# Gamer.net
KiCad netlist of a schematic drawn in EAGLE
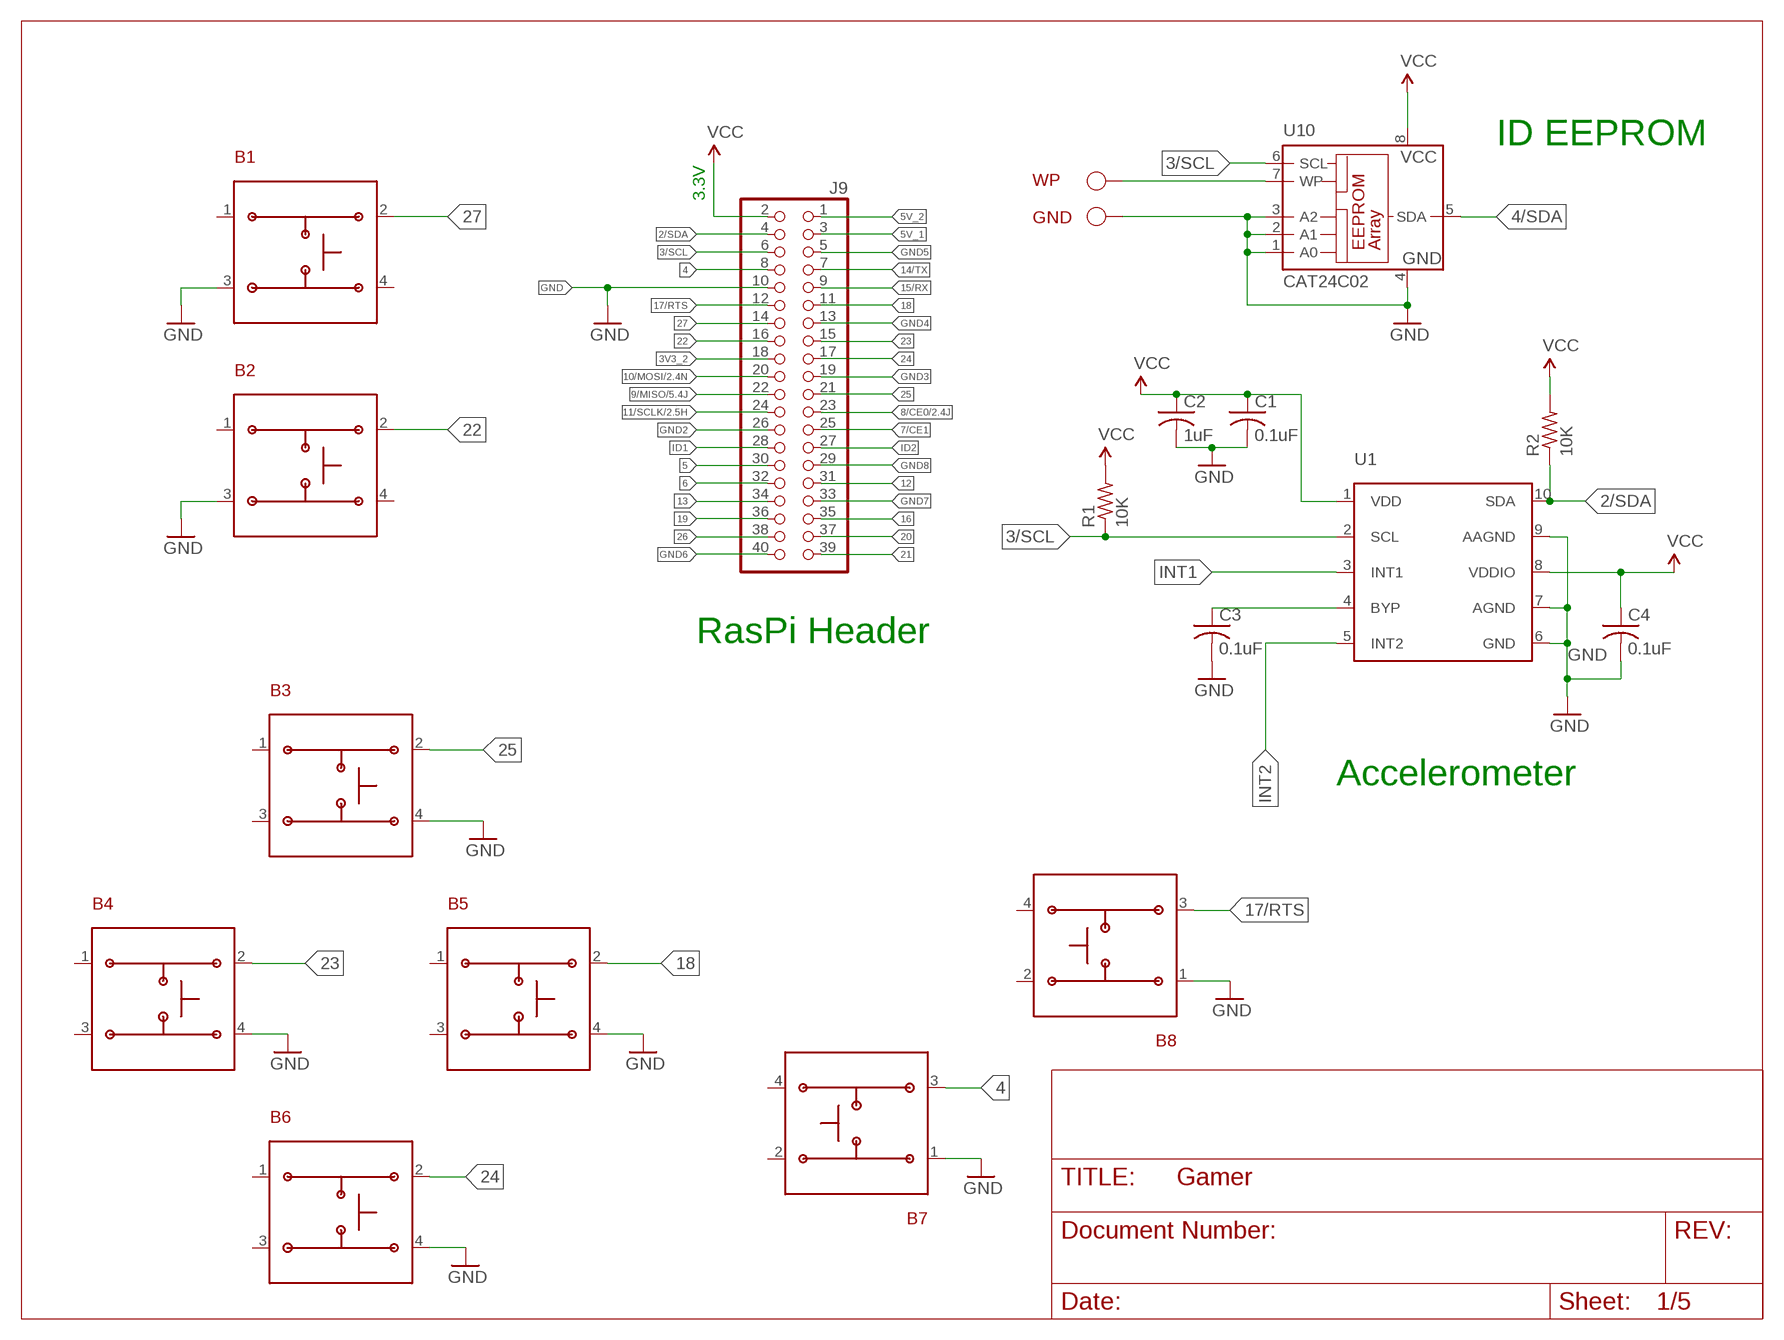
[diagram p0: schematic, sheet 1]
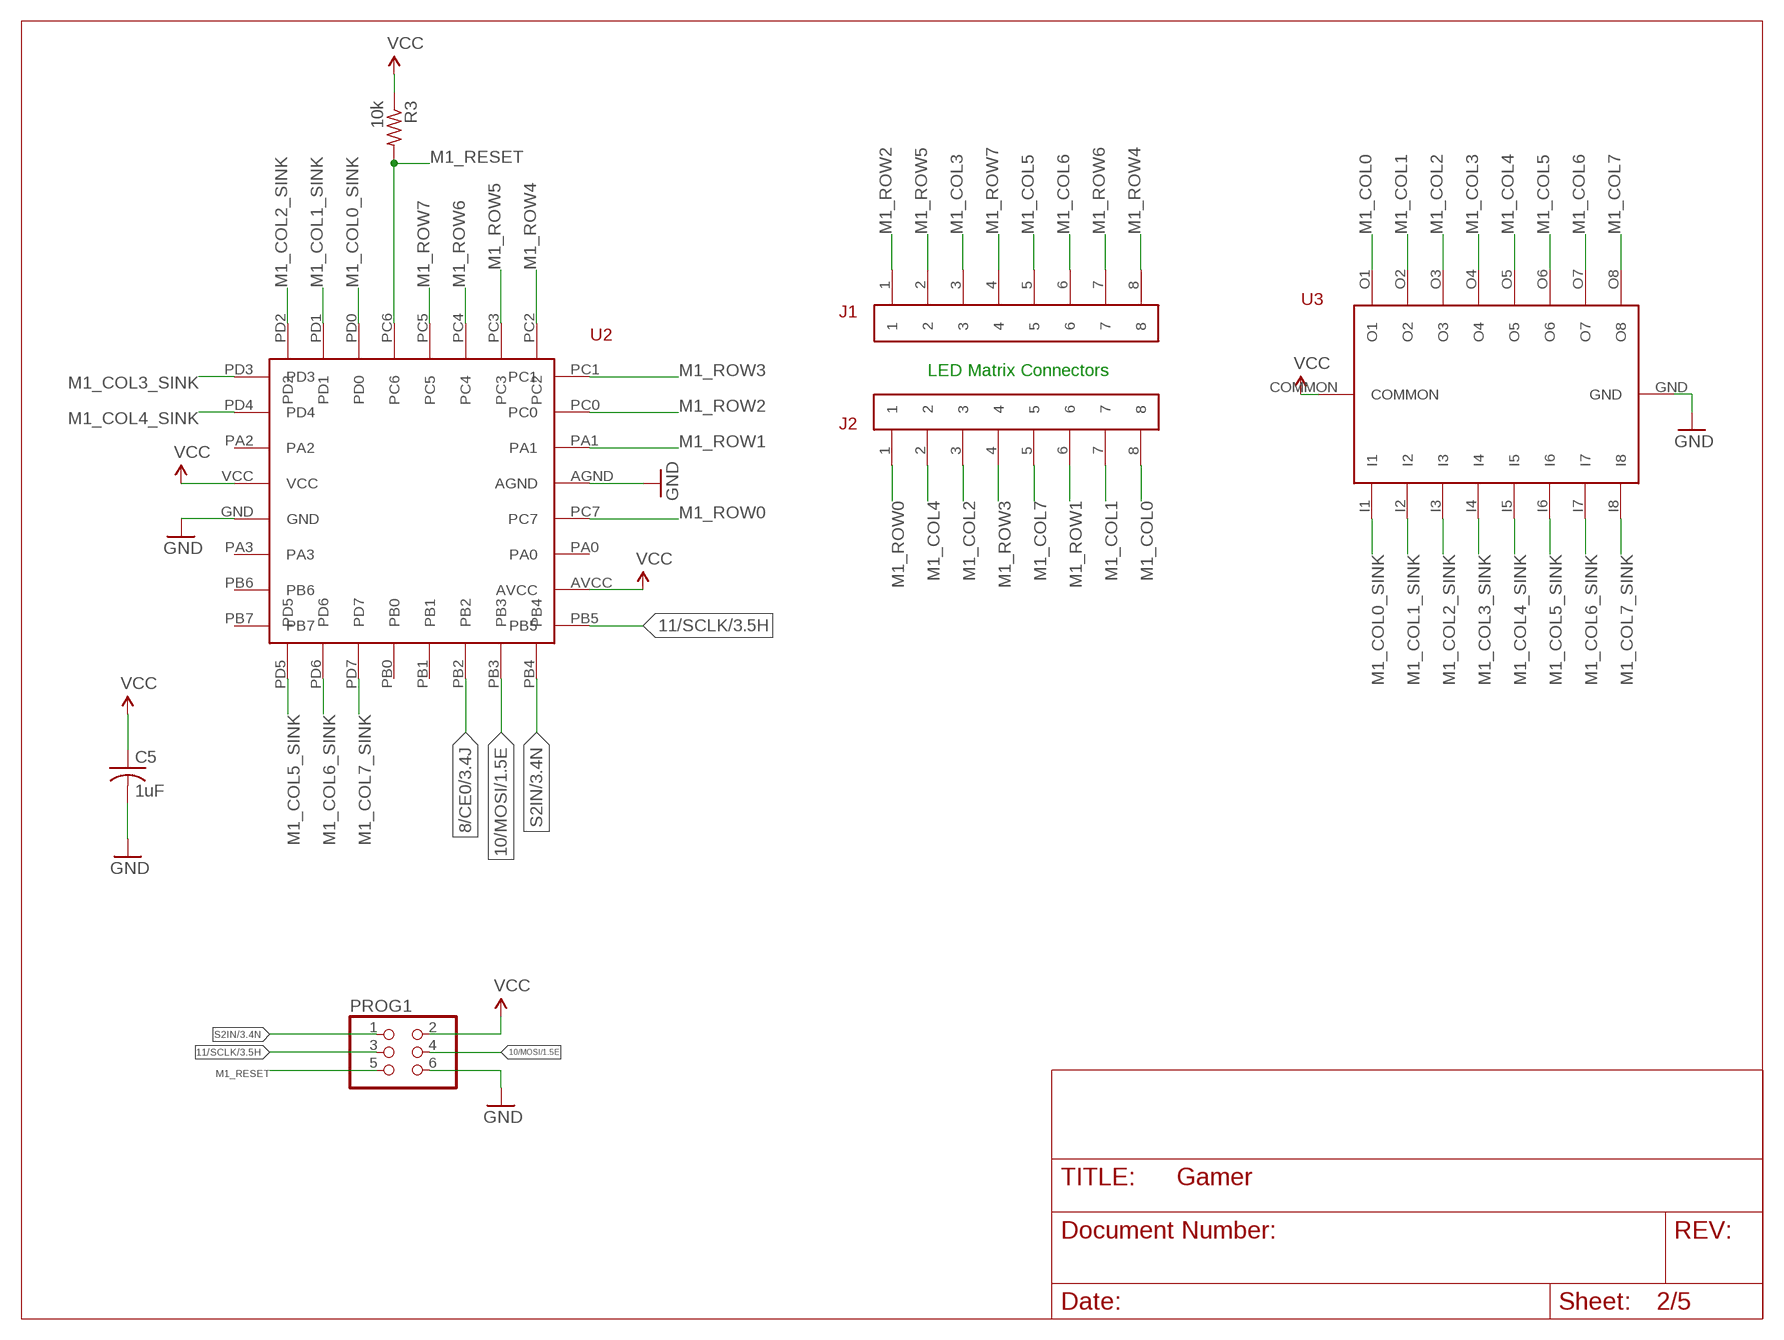
[diagram p1: schematic, sheet 2]
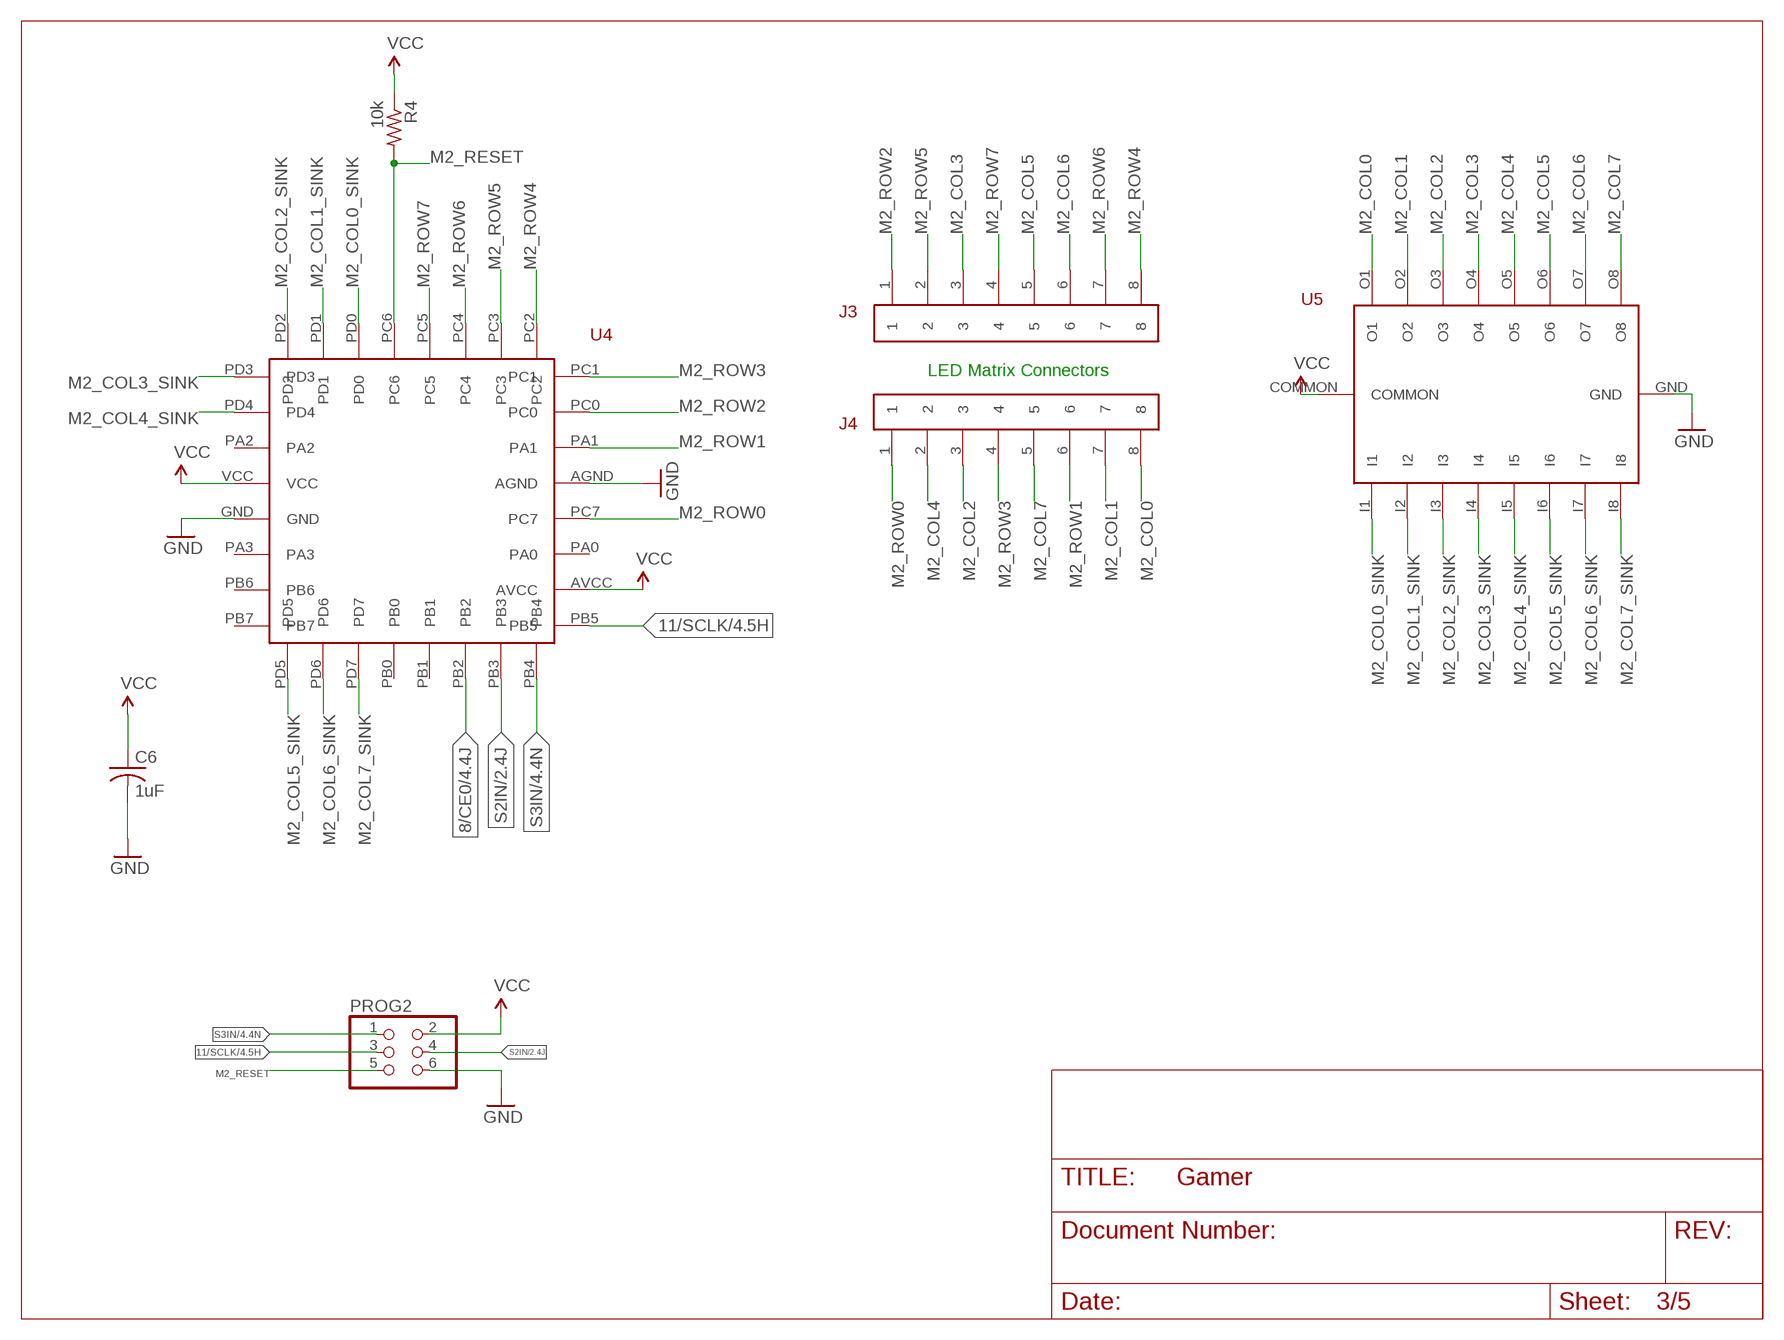
[diagram p2: schematic, sheet 3]
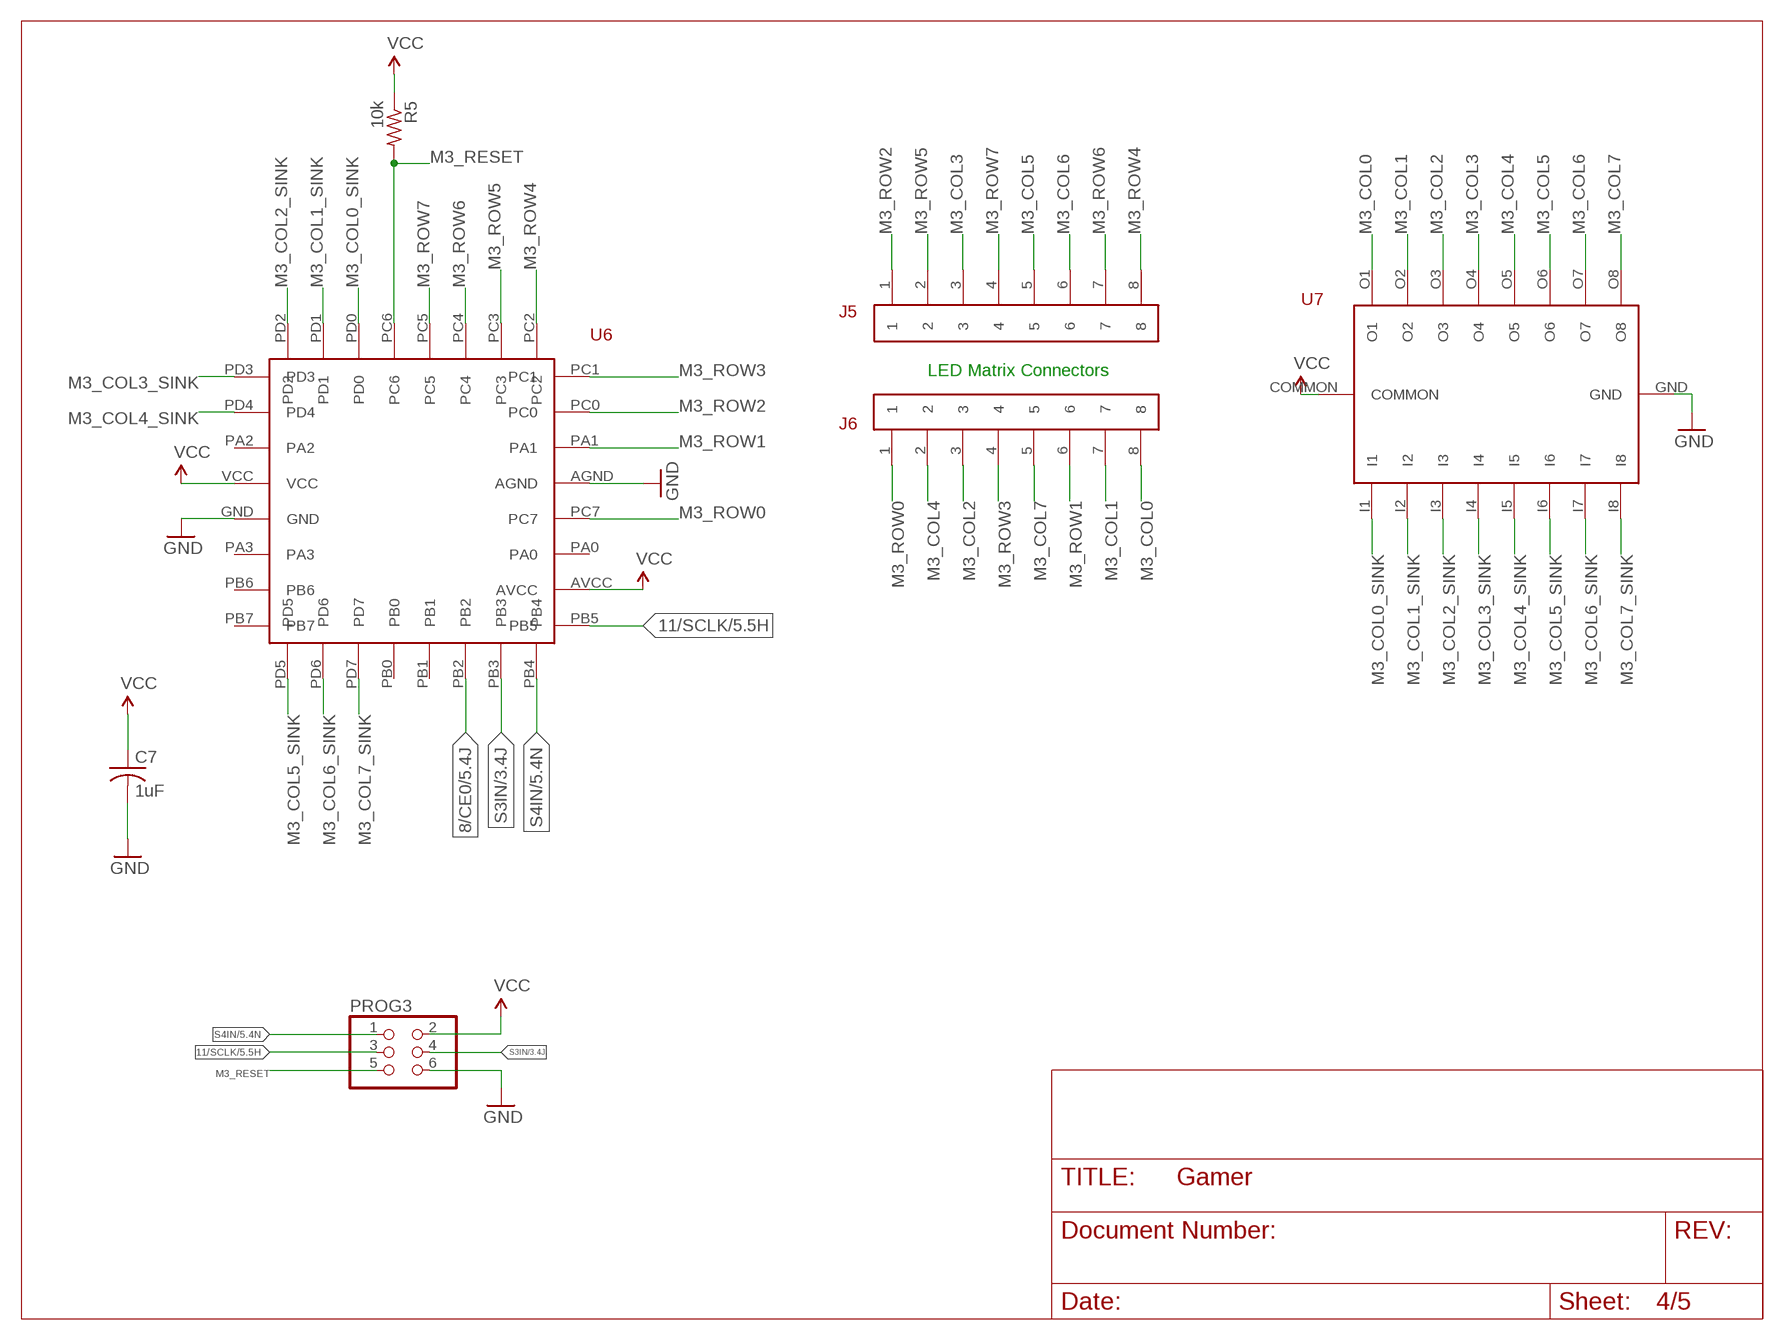
[diagram p3: schematic, sheet 4]
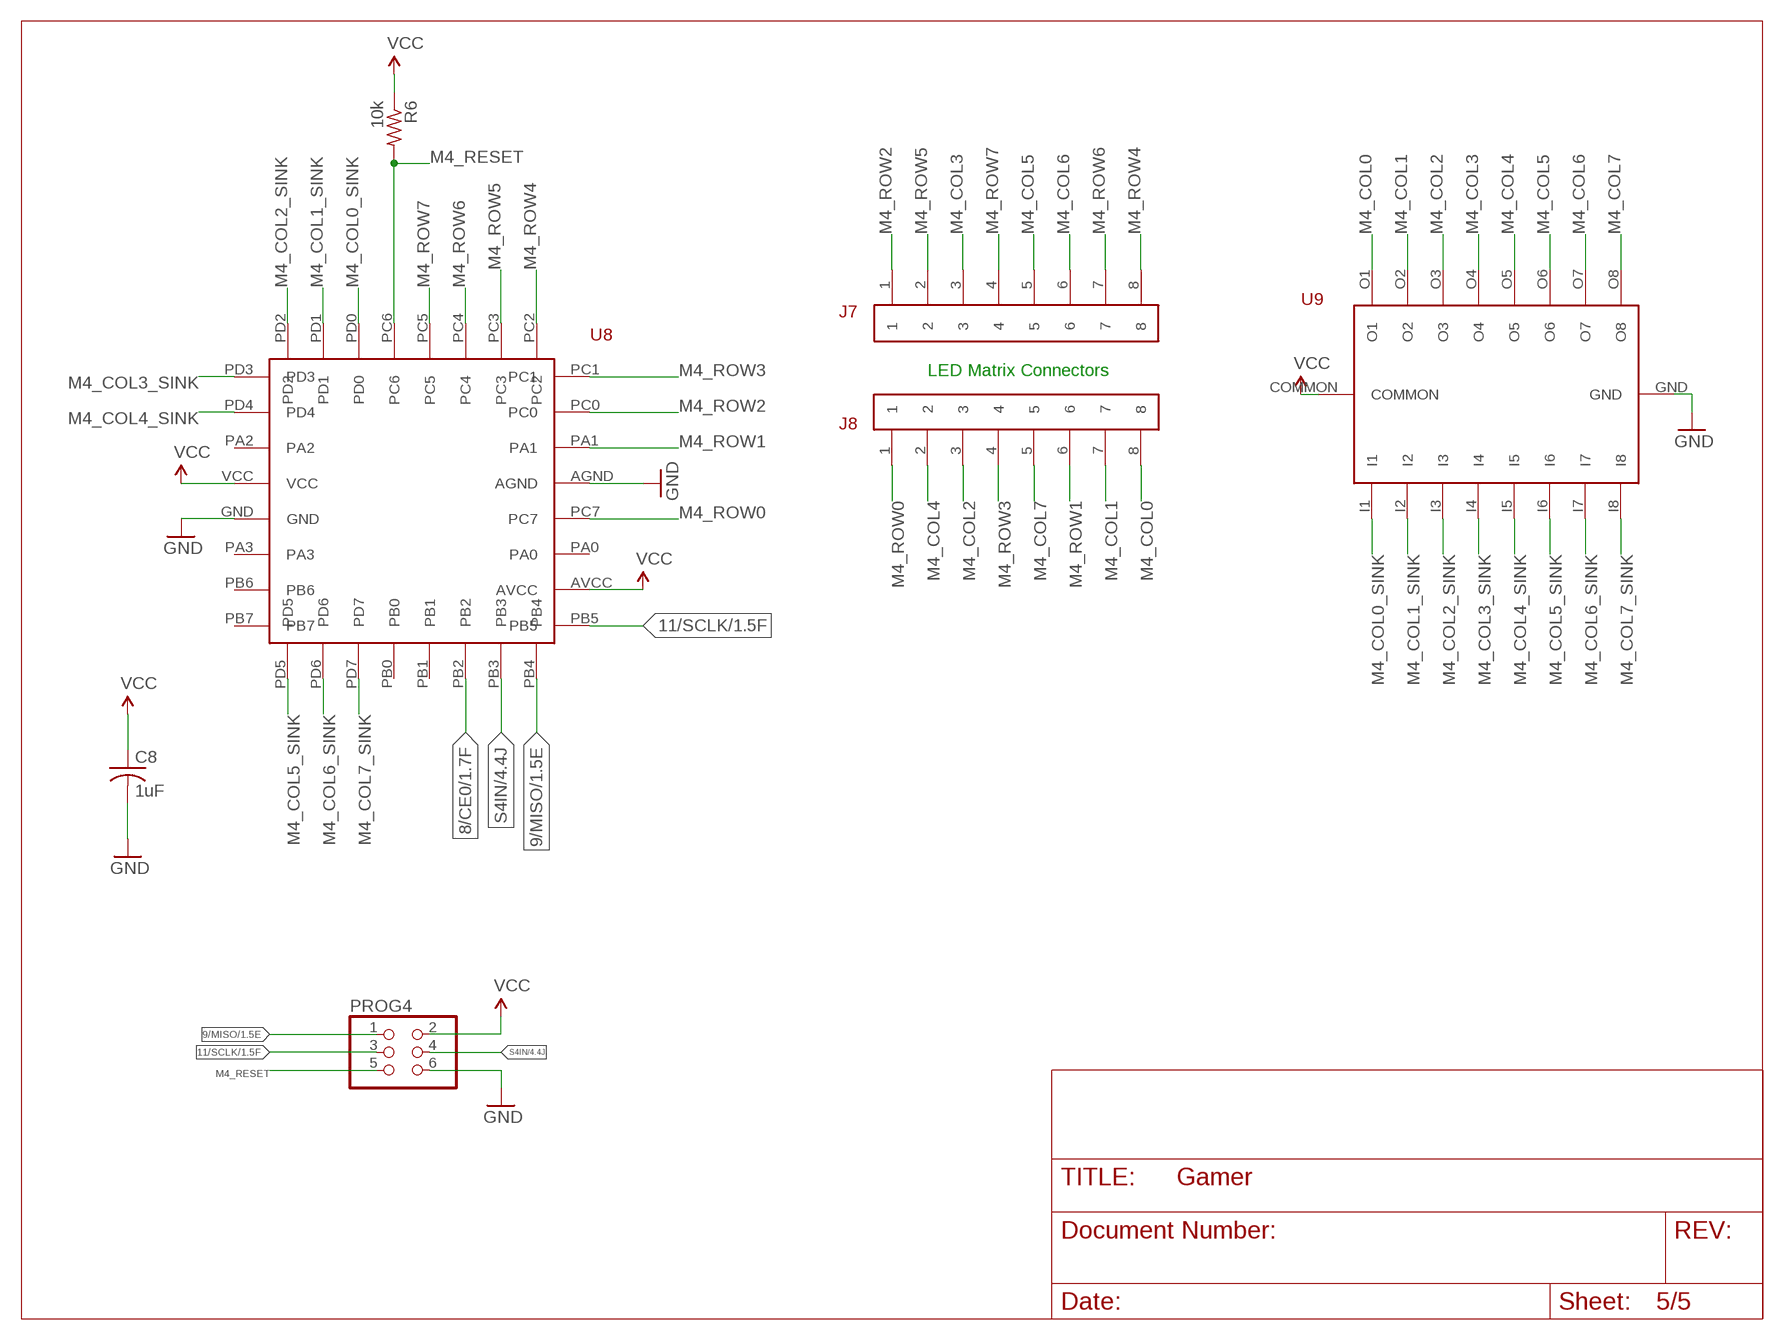
[diagram p4: schematic, sheet 5]

(export (version "E")
  (design (tool "Eeschema 10.0.6"))
  (components
    (comp (ref "C5")
      (value "1uF")
      (footprint "eagle-import:C0603")
      (libsource (lib "eagle-import") (part "resistor_C-USC0603"))
    )
    (comp (ref "J1")
      (value "HEADER-1X8")
      (footprint "eagle-import:HEADER-1X8")
      (libsource (lib "eagle-import") (part "HEADER-1X8"))
    )
    (comp (ref "J2")
      (value "HEADER-1X8")
      (footprint "eagle-import:HEADER-1X8")
      (libsource (lib "eagle-import") (part "HEADER-1X8"))
    )
    (comp (ref "PROG1")
      (value "NONE")
      (footprint "eagle-import:2X03")
      (libsource (lib "eagle-import") (part "PINHD-2X3"))
    )
    (comp (ref "R3")
      (value "10k")
      (footprint "eagle-import:R0603")
      (libsource (lib "eagle-import") (part "resistor_R-US_R0603"))
    )
    (comp (ref "U2")
      (value "ATTINY48")
      (footprint "eagle-import:ATTINY48")
      (libsource (lib "eagle-import") (part "ATTINY48"))
    )
    (comp (ref "U3")
      (value "ULN2803AFWG")
      (footprint "eagle-import:ULN2803AFWG")
      (libsource (lib "eagle-import") (part "ULN2803AFWG"))
    )
    (comp (ref "C6")
      (value "1uF")
      (footprint "eagle-import:C0603")
      (libsource (lib "eagle-import") (part "resistor_C-USC0603"))
    )
    (comp (ref "J3")
      (value "HEADER-1X8")
      (footprint "eagle-import:HEADER-1X8")
      (libsource (lib "eagle-import") (part "HEADER-1X8"))
    )
    (comp (ref "J4")
      (value "HEADER-1X8")
      (footprint "eagle-import:HEADER-1X8")
      (libsource (lib "eagle-import") (part "HEADER-1X8"))
    )
    (comp (ref "PROG2")
      (value "NONE")
      (footprint "eagle-import:2X03")
      (libsource (lib "eagle-import") (part "PINHD-2X3"))
    )
    (comp (ref "R4")
      (value "10k")
      (footprint "eagle-import:R0603")
      (libsource (lib "eagle-import") (part "resistor_R-US_R0603"))
    )
    (comp (ref "U4")
      (value "ATTINY48")
      (footprint "eagle-import:ATTINY48")
      (libsource (lib "eagle-import") (part "ATTINY48"))
    )
    (comp (ref "U5")
      (value "ULN2803AFWG")
      (footprint "eagle-import:ULN2803AFWG")
      (libsource (lib "eagle-import") (part "ULN2803AFWG"))
    )
    (comp (ref "B1")
      (value "6X6MM_BUTTON")
      (footprint "eagle-import:6X6MM_BUTTON")
      (libsource (lib "eagle-import") (part "6X6MM_BUTTON"))
    )
    (comp (ref "B2")
      (value "6X6MM_BUTTON")
      (footprint "eagle-import:6X6MM_BUTTON")
      (libsource (lib "eagle-import") (part "6X6MM_BUTTON"))
    )
    (comp (ref "B3")
      (value "12X12MM_BUTTON")
      (footprint "eagle-import:12X12MM_BUTTON")
      (libsource (lib "eagle-import") (part "12X12MM_BUTTON"))
    )
    (comp (ref "B4")
      (value "12X12MM_BUTTON")
      (footprint "eagle-import:12X12MM_BUTTON")
      (libsource (lib "eagle-import") (part "12X12MM_BUTTON"))
    )
    (comp (ref "B5")
      (value "12X12MM_BUTTON")
      (footprint "eagle-import:12X12MM_BUTTON")
      (libsource (lib "eagle-import") (part "12X12MM_BUTTON"))
    )
    (comp (ref "B6")
      (value "12X12MM_BUTTON")
      (footprint "eagle-import:12X12MM_BUTTON")
      (libsource (lib "eagle-import") (part "12X12MM_BUTTON"))
    )
    (comp (ref "B7")
      (value "12X12MM_BUTTON")
      (footprint "eagle-import:12X12MM_BUTTON")
      (libsource (lib "eagle-import") (part "12X12MM_BUTTON"))
    )
    (comp (ref "B8")
      (value "12X12MM_BUTTON")
      (footprint "eagle-import:12X12MM_BUTTON")
      (libsource (lib "eagle-import") (part "12X12MM_BUTTON"))
    )
    (comp (ref "C1")
      (value "0.1uF")
      (footprint "eagle-import:C0603")
      (libsource (lib "eagle-import") (part "C-USC0603"))
    )
    (comp (ref "C2")
      (value "1uF")
      (footprint "eagle-import:C0603")
      (libsource (lib "eagle-import") (part "C-USC0603"))
    )
    (comp (ref "C3")
      (value "0.1uF")
      (footprint "eagle-import:C0603")
      (libsource (lib "eagle-import") (part "C-USC0603"))
    )
    (comp (ref "C4")
      (value "0.1uF")
      (footprint "eagle-import:C0603")
      (libsource (lib "eagle-import") (part "C-USC0603"))
    )
    (comp (ref "GND")
      (value "TESTPAD")
      (footprint "eagle-import:TESTPAD")
      (libsource (lib "eagle-import") (part "TESTPAD"))
    )
    (comp (ref "J9")
      (value "PINHD-2X20")
      (footprint "eagle-import:2X20")
      (libsource (lib "eagle-import") (part "PINHD-2X20"))
    )
    (comp (ref "R1")
      (value "10K")
      (footprint "eagle-import:R0603")
      (libsource (lib "eagle-import") (part "R-US_R0603"))
    )
    (comp (ref "R2")
      (value "10K")
      (footprint "eagle-import:R0603")
      (libsource (lib "eagle-import") (part "R-US_R0603"))
    )
    (comp (ref "U1")
      (value "MMA8653FCR1")
      (footprint "eagle-import:MMA8653FCR1")
      (libsource (lib "eagle-import") (part "MMA8653FCR1"))
    )
    (comp (ref "U10")
      (value "CAT24C02")
      (footprint "eagle-import:TSSOP8")
      (fields (field (name "MF") "MICROCHIP") (field (name "MPN") "24LC64X-I/ST"))
      (libsource (lib "eagle-import") (part "24STLC64"))
    )
    (comp (ref "WP")
      (value "TESTPAD")
      (footprint "eagle-import:TESTPAD")
      (libsource (lib "eagle-import") (part "TESTPAD"))
    )
    (comp (ref "C7")
      (value "1uF")
      (footprint "eagle-import:C0603")
      (libsource (lib "eagle-import") (part "resistor_C-USC0603"))
    )
    (comp (ref "J5")
      (value "HEADER-1X8")
      (footprint "eagle-import:HEADER-1X8")
      (libsource (lib "eagle-import") (part "HEADER-1X8"))
    )
    (comp (ref "J6")
      (value "HEADER-1X8")
      (footprint "eagle-import:HEADER-1X8")
      (libsource (lib "eagle-import") (part "HEADER-1X8"))
    )
    (comp (ref "PROG3")
      (value "NONE")
      (footprint "eagle-import:2X03")
      (libsource (lib "eagle-import") (part "PINHD-2X3"))
    )
    (comp (ref "R5")
      (value "10k")
      (footprint "eagle-import:R0603")
      (libsource (lib "eagle-import") (part "resistor_R-US_R0603"))
    )
    (comp (ref "U6")
      (value "ATTINY48")
      (footprint "eagle-import:ATTINY48")
      (libsource (lib "eagle-import") (part "ATTINY48"))
    )
    (comp (ref "U7")
      (value "ULN2803AFWG")
      (footprint "eagle-import:ULN2803AFWG")
      (libsource (lib "eagle-import") (part "ULN2803AFWG"))
    )
    (comp (ref "C8")
      (value "1uF")
      (footprint "eagle-import:C0603")
      (libsource (lib "eagle-import") (part "resistor_C-USC0603"))
    )
    (comp (ref "J7")
      (value "HEADER-1X8")
      (footprint "eagle-import:HEADER-1X8")
      (libsource (lib "eagle-import") (part "HEADER-1X8"))
    )
    (comp (ref "J8")
      (value "HEADER-1X8")
      (footprint "eagle-import:HEADER-1X8")
      (libsource (lib "eagle-import") (part "HEADER-1X8"))
    )
    (comp (ref "PROG4")
      (value "NONE")
      (footprint "eagle-import:2X03")
      (libsource (lib "eagle-import") (part "PINHD-2X3"))
    )
    (comp (ref "R6")
      (value "10k")
      (footprint "eagle-import:R0603")
      (libsource (lib "eagle-import") (part "resistor_R-US_R0603"))
    )
    (comp (ref "U8")
      (value "ATTINY48")
      (footprint "eagle-import:ATTINY48")
      (libsource (lib "eagle-import") (part "ATTINY48"))
    )
    (comp (ref "U9")
      (value "ULN2803AFWG")
      (footprint "eagle-import:ULN2803AFWG")
      (libsource (lib "eagle-import") (part "ULN2803AFWG"))
    )
  )
  (nets
    (net (code "1") (name "2{slash}SDA") (class "Default")
      (node (ref "J9") (pin "4") (pinfunction "4_4") (pintype "passive"))
      (node (ref "R2") (pin "1") (pinfunction "1_1") (pintype "passive"))
      (node (ref "U1") (pin "10") (pinfunction "SDA_10") (pintype "bidirectional"))
    )
    (net (code "2") (name "3V3_2") (class "Default")
      (node (ref "J9") (pin "18") (pinfunction "18_18") (pintype "passive"))
    )
    (net (code "3") (name "3{slash}SCL") (class "Default")
      (node (ref "J9") (pin "6") (pinfunction "6_6") (pintype "passive"))
      (node (ref "R1") (pin "1") (pinfunction "1_1") (pintype "passive"))
      (node (ref "U1") (pin "2") (pinfunction "SCL_2") (pintype "bidirectional"))
      (node (ref "U10") (pin "6") (pinfunction "SCL_6") (pintype "input"))
    )
    (net (code "4") (name "4") (class "Default")
      (node (ref "B7") (pin "3") (pinfunction "3_3") (pintype "bidirectional"))
      (node (ref "J9") (pin "8") (pinfunction "8_8") (pintype "passive"))
    )
    (net (code "5") (name "4{slash}SDA") (class "Default")
      (node (ref "U10") (pin "5") (pinfunction "SDA_5") (pintype "bidirectional"))
    )
    (net (code "6") (name "5") (class "Default")
      (node (ref "J9") (pin "30") (pinfunction "30_30") (pintype "passive"))
    )
    (net (code "7") (name "5V_1") (class "Default")
      (node (ref "J9") (pin "3") (pinfunction "3_3") (pintype "passive"))
    )
    (net (code "8") (name "5V_2") (class "Default")
      (node (ref "J9") (pin "1") (pinfunction "1_1") (pintype "passive"))
    )
    (net (code "9") (name "6") (class "Default")
      (node (ref "J9") (pin "32") (pinfunction "32_32") (pintype "passive"))
    )
    (net (code "10") (name "7{slash}CE1") (class "Default")
      (node (ref "J9") (pin "25") (pinfunction "25_25") (pintype "passive"))
    )
    (net (code "11") (name "8{slash}CE0") (class "Default")
      (node (ref "J9") (pin "23") (pinfunction "23_23") (pintype "passive"))
      (node (ref "U2") (pin "PB2") (pinfunction "PB2_PB2") (pintype "bidirectional"))
      (node (ref "U4") (pin "PB2") (pinfunction "PB2_PB2") (pintype "bidirectional"))
      (node (ref "U6") (pin "PB2") (pinfunction "PB2_PB2") (pintype "bidirectional"))
      (node (ref "U8") (pin "PB2") (pinfunction "PB2_PB2") (pintype "bidirectional"))
    )
    (net (code "12") (name "9{slash}MISO") (class "Default")
      (node (ref "J9") (pin "22") (pinfunction "22_22") (pintype "passive"))
      (node (ref "PROG4") (pin "1") (pinfunction "1_1") (pintype "passive"))
      (node (ref "U8") (pin "PB4") (pinfunction "PB4_PB4") (pintype "bidirectional"))
    )
    (net (code "13") (name "10{slash}MOSI") (class "Default")
      (node (ref "J9") (pin "20") (pinfunction "20_20") (pintype "passive"))
      (node (ref "PROG1") (pin "4") (pinfunction "4_4") (pintype "passive"))
      (node (ref "U2") (pin "PB3") (pinfunction "PB3_PB3") (pintype "bidirectional"))
    )
    (net (code "14") (name "11{slash}SCLK") (class "Default")
      (node (ref "J9") (pin "24") (pinfunction "24_24") (pintype "passive"))
      (node (ref "PROG1") (pin "3") (pinfunction "3_3") (pintype "passive"))
      (node (ref "PROG2") (pin "3") (pinfunction "3_3") (pintype "passive"))
      (node (ref "PROG3") (pin "3") (pinfunction "3_3") (pintype "passive"))
      (node (ref "PROG4") (pin "3") (pinfunction "3_3") (pintype "passive"))
      (node (ref "U2") (pin "PB5") (pinfunction "PB5_PB5") (pintype "bidirectional"))
      (node (ref "U4") (pin "PB5") (pinfunction "PB5_PB5") (pintype "bidirectional"))
      (node (ref "U6") (pin "PB5") (pinfunction "PB5_PB5") (pintype "bidirectional"))
      (node (ref "U8") (pin "PB5") (pinfunction "PB5_PB5") (pintype "bidirectional"))
    )
    (net (code "15") (name "12") (class "Default")
      (node (ref "J9") (pin "31") (pinfunction "31_31") (pintype "passive"))
    )
    (net (code "16") (name "13") (class "Default")
      (node (ref "J9") (pin "34") (pinfunction "34_34") (pintype "passive"))
    )
    (net (code "17") (name "14{slash}TX") (class "Default")
      (node (ref "J9") (pin "7") (pinfunction "7_7") (pintype "passive"))
    )
    (net (code "18") (name "15{slash}RX") (class "Default")
      (node (ref "J9") (pin "9") (pinfunction "9_9") (pintype "passive"))
    )
    (net (code "19") (name "16") (class "Default")
      (node (ref "J9") (pin "35") (pinfunction "35_35") (pintype "passive"))
    )
    (net (code "20") (name "17{slash}RTS") (class "Default")
      (node (ref "B8") (pin "3") (pinfunction "3_3") (pintype "bidirectional"))
      (node (ref "J9") (pin "12") (pinfunction "12_12") (pintype "passive"))
    )
    (net (code "21") (name "18") (class "Default")
      (node (ref "B5") (pin "2") (pinfunction "2_2") (pintype "bidirectional"))
      (node (ref "J9") (pin "11") (pinfunction "11_11") (pintype "passive"))
    )
    (net (code "22") (name "19") (class "Default")
      (node (ref "J9") (pin "36") (pinfunction "36_36") (pintype "passive"))
    )
    (net (code "23") (name "20") (class "Default")
      (node (ref "J9") (pin "37") (pinfunction "37_37") (pintype "passive"))
    )
    (net (code "24") (name "21") (class "Default")
      (node (ref "J9") (pin "39") (pinfunction "39_39") (pintype "passive"))
    )
    (net (code "25") (name "22") (class "Default")
      (node (ref "B2") (pin "2") (pinfunction "2_2") (pintype "bidirectional"))
      (node (ref "J9") (pin "16") (pinfunction "16_16") (pintype "passive"))
    )
    (net (code "26") (name "23") (class "Default")
      (node (ref "B4") (pin "2") (pinfunction "2_2") (pintype "bidirectional"))
      (node (ref "J9") (pin "15") (pinfunction "15_15") (pintype "passive"))
    )
    (net (code "27") (name "24") (class "Default")
      (node (ref "B6") (pin "2") (pinfunction "2_2") (pintype "bidirectional"))
      (node (ref "J9") (pin "17") (pinfunction "17_17") (pintype "passive"))
    )
    (net (code "28") (name "25") (class "Default")
      (node (ref "B3") (pin "2") (pinfunction "2_2") (pintype "bidirectional"))
      (node (ref "J9") (pin "21") (pinfunction "21_21") (pintype "passive"))
    )
    (net (code "29") (name "26") (class "Default")
      (node (ref "J9") (pin "38") (pinfunction "38_38") (pintype "passive"))
    )
    (net (code "30") (name "27") (class "Default")
      (node (ref "B1") (pin "2") (pinfunction "2_2") (pintype "bidirectional"))
      (node (ref "J9") (pin "14") (pinfunction "14_14") (pintype "passive"))
    )
    (net (code "31") (name "GND") (class "Default")
      (node (ref "B1") (pin "3") (pinfunction "3_3") (pintype "bidirectional"))
      (node (ref "B2") (pin "3") (pinfunction "3_3") (pintype "bidirectional"))
      (node (ref "B3") (pin "4") (pinfunction "4_4") (pintype "bidirectional"))
      (node (ref "B4") (pin "4") (pinfunction "4_4") (pintype "bidirectional"))
      (node (ref "B5") (pin "4") (pinfunction "4_4") (pintype "bidirectional"))
      (node (ref "B6") (pin "4") (pinfunction "4_4") (pintype "bidirectional"))
      (node (ref "B7") (pin "1") (pinfunction "1_1") (pintype "bidirectional"))
      (node (ref "B8") (pin "1") (pinfunction "1_1") (pintype "bidirectional"))
      (node (ref "C1") (pin "2") (pinfunction "2_2") (pintype "passive"))
      (node (ref "C2") (pin "2") (pinfunction "2_2") (pintype "passive"))
      (node (ref "C3") (pin "2") (pinfunction "2_2") (pintype "passive"))
      (node (ref "C4") (pin "2") (pinfunction "2_2") (pintype "passive"))
      (node (ref "C5") (pin "2") (pinfunction "2_2") (pintype "passive"))
      (node (ref "C6") (pin "2") (pinfunction "2_2") (pintype "passive"))
      (node (ref "C7") (pin "2") (pinfunction "2_2") (pintype "passive"))
      (node (ref "C8") (pin "2") (pinfunction "2_2") (pintype "passive"))
      (node (ref "GND") (pin "1") (pinfunction "P$1_1") (pintype "bidirectional"))
      (node (ref "J9") (pin "10") (pinfunction "10_10") (pintype "passive"))
      (node (ref "PROG1") (pin "6") (pinfunction "6_6") (pintype "passive"))
      (node (ref "PROG2") (pin "6") (pinfunction "6_6") (pintype "passive"))
      (node (ref "PROG3") (pin "6") (pinfunction "6_6") (pintype "passive"))
      (node (ref "PROG4") (pin "6") (pinfunction "6_6") (pintype "passive"))
      (node (ref "U1") (pin "6") (pinfunction "GND_6") (pintype "bidirectional"))
      (node (ref "U1") (pin "7") (pinfunction "AGND_7") (pintype "bidirectional"))
      (node (ref "U1") (pin "9") (pinfunction "AAGND_9") (pintype "bidirectional"))
      (node (ref "U10") (pin "1") (pinfunction "A0_1") (pintype "input"))
      (node (ref "U10") (pin "2") (pinfunction "A1_2") (pintype "input"))
      (node (ref "U10") (pin "3") (pinfunction "A2_3") (pintype "input"))
      (node (ref "U10") (pin "4") (pinfunction "GND_4") (pintype "power_in"))
      (node (ref "U2") (pin "AGND") (pinfunction "AGND_AGND") (pintype "bidirectional"))
      (node (ref "U2") (pin "GND") (pinfunction "GND_GND") (pintype "bidirectional"))
      (node (ref "U3") (pin "GND") (pinfunction "GND_GND") (pintype "bidirectional"))
      (node (ref "U4") (pin "AGND") (pinfunction "AGND_AGND") (pintype "bidirectional"))
      (node (ref "U4") (pin "GND") (pinfunction "GND_GND") (pintype "bidirectional"))
      (node (ref "U5") (pin "GND") (pinfunction "GND_GND") (pintype "bidirectional"))
      (node (ref "U6") (pin "AGND") (pinfunction "AGND_AGND") (pintype "bidirectional"))
      (node (ref "U6") (pin "GND") (pinfunction "GND_GND") (pintype "bidirectional"))
      (node (ref "U7") (pin "GND") (pinfunction "GND_GND") (pintype "bidirectional"))
      (node (ref "U8") (pin "AGND") (pinfunction "AGND_AGND") (pintype "bidirectional"))
      (node (ref "U8") (pin "GND") (pinfunction "GND_GND") (pintype "bidirectional"))
      (node (ref "U9") (pin "GND") (pinfunction "GND_GND") (pintype "bidirectional"))
    )
    (net (code "32") (name "GND2") (class "Default")
      (node (ref "J9") (pin "26") (pinfunction "26_26") (pintype "passive"))
    )
    (net (code "33") (name "GND3") (class "Default")
      (node (ref "J9") (pin "19") (pinfunction "19_19") (pintype "passive"))
    )
    (net (code "34") (name "GND4") (class "Default")
      (node (ref "J9") (pin "13") (pinfunction "13_13") (pintype "passive"))
    )
    (net (code "35") (name "GND5") (class "Default")
      (node (ref "J9") (pin "5") (pinfunction "5_5") (pintype "passive"))
    )
    (net (code "36") (name "GND6") (class "Default")
      (node (ref "J9") (pin "40") (pinfunction "40_40") (pintype "passive"))
    )
    (net (code "37") (name "GND7") (class "Default")
      (node (ref "J9") (pin "33") (pinfunction "33_33") (pintype "passive"))
    )
    (net (code "38") (name "GND8") (class "Default")
      (node (ref "J9") (pin "29") (pinfunction "29_29") (pintype "passive"))
    )
    (net (code "39") (name "ID1") (class "Default")
      (node (ref "J9") (pin "28") (pinfunction "28_28") (pintype "passive"))
    )
    (net (code "40") (name "ID2") (class "Default")
      (node (ref "J9") (pin "27") (pinfunction "27_27") (pintype "passive"))
    )
    (net (code "41") (name "INT1") (class "Default")
      (node (ref "U1") (pin "3") (pinfunction "INT1_3") (pintype "bidirectional"))
    )
    (net (code "42") (name "INT2") (class "Default")
      (node (ref "U1") (pin "5") (pinfunction "INT2_5") (pintype "bidirectional"))
    )
    (net (code "43") (name "M1_COL0") (class "Default")
      (node (ref "J2") (pin "8") (pinfunction "8_8") (pintype "bidirectional"))
      (node (ref "U3") (pin "O1") (pinfunction "O1_O1") (pintype "bidirectional"))
    )
    (net (code "44") (name "M1_COL0_SINK") (class "Default")
      (node (ref "U2") (pin "PD0") (pinfunction "PD0_PD0") (pintype "bidirectional"))
      (node (ref "U3") (pin "I1") (pinfunction "I1_I1") (pintype "bidirectional"))
    )
    (net (code "45") (name "M1_COL1") (class "Default")
      (node (ref "J2") (pin "7") (pinfunction "7_7") (pintype "bidirectional"))
      (node (ref "U3") (pin "O2") (pinfunction "O2_O2") (pintype "bidirectional"))
    )
    (net (code "46") (name "M1_COL1_SINK") (class "Default")
      (node (ref "U2") (pin "PD1") (pinfunction "PD1_PD1") (pintype "bidirectional"))
      (node (ref "U3") (pin "I2") (pinfunction "I2_I2") (pintype "bidirectional"))
    )
    (net (code "47") (name "M1_COL2") (class "Default")
      (node (ref "J2") (pin "3") (pinfunction "3_3") (pintype "bidirectional"))
      (node (ref "U3") (pin "O3") (pinfunction "O3_O3") (pintype "bidirectional"))
    )
    (net (code "48") (name "M1_COL2_SINK") (class "Default")
      (node (ref "U2") (pin "PD2") (pinfunction "PD2_PD2") (pintype "bidirectional"))
      (node (ref "U3") (pin "I3") (pinfunction "I3_I3") (pintype "bidirectional"))
    )
    (net (code "49") (name "M1_COL3") (class "Default")
      (node (ref "J1") (pin "3") (pinfunction "3_3") (pintype "bidirectional"))
      (node (ref "U3") (pin "O4") (pinfunction "O4_O4") (pintype "bidirectional"))
    )
    (net (code "50") (name "M1_COL3_SINK") (class "Default")
      (node (ref "U2") (pin "PD3") (pinfunction "PD3_PD3") (pintype "bidirectional"))
      (node (ref "U3") (pin "I4") (pinfunction "I4_I4") (pintype "bidirectional"))
    )
    (net (code "51") (name "M1_COL4") (class "Default")
      (node (ref "J2") (pin "2") (pinfunction "2_2") (pintype "bidirectional"))
      (node (ref "U3") (pin "O5") (pinfunction "O5_O5") (pintype "bidirectional"))
    )
    (net (code "52") (name "M1_COL4_SINK") (class "Default")
      (node (ref "U2") (pin "PD4") (pinfunction "PD4_PD4") (pintype "bidirectional"))
      (node (ref "U3") (pin "I5") (pinfunction "I5_I5") (pintype "bidirectional"))
    )
    (net (code "53") (name "M1_COL5") (class "Default")
      (node (ref "J1") (pin "5") (pinfunction "5_5") (pintype "bidirectional"))
      (node (ref "U3") (pin "O6") (pinfunction "O6_O6") (pintype "bidirectional"))
    )
    (net (code "54") (name "M1_COL5_SINK") (class "Default")
      (node (ref "U2") (pin "PD5") (pinfunction "PD5_PD5") (pintype "bidirectional"))
      (node (ref "U3") (pin "I6") (pinfunction "I6_I6") (pintype "bidirectional"))
    )
    (net (code "55") (name "M1_COL6") (class "Default")
      (node (ref "J1") (pin "6") (pinfunction "6_6") (pintype "bidirectional"))
      (node (ref "U3") (pin "O7") (pinfunction "O7_O7") (pintype "bidirectional"))
    )
    (net (code "56") (name "M1_COL6_SINK") (class "Default")
      (node (ref "U2") (pin "PD6") (pinfunction "PD6_PD6") (pintype "bidirectional"))
      (node (ref "U3") (pin "I7") (pinfunction "I7_I7") (pintype "bidirectional"))
    )
    (net (code "57") (name "M1_COL7") (class "Default")
      (node (ref "J2") (pin "5") (pinfunction "5_5") (pintype "bidirectional"))
      (node (ref "U3") (pin "O8") (pinfunction "O8_O8") (pintype "bidirectional"))
    )
    (net (code "58") (name "M1_COL7_SINK") (class "Default")
      (node (ref "U2") (pin "PD7") (pinfunction "PD7_PD7") (pintype "bidirectional"))
      (node (ref "U3") (pin "I8") (pinfunction "I8_I8") (pintype "bidirectional"))
    )
    (net (code "59") (name "M1_RESET") (class "Default")
      (node (ref "PROG1") (pin "5") (pinfunction "5_5") (pintype "passive"))
      (node (ref "R3") (pin "2") (pinfunction "2_2") (pintype "passive"))
      (node (ref "U2") (pin "PC6") (pinfunction "PC6_PC6") (pintype "bidirectional"))
    )
    (net (code "60") (name "M1_ROW0") (class "Default")
      (node (ref "J2") (pin "1") (pinfunction "1_1") (pintype "bidirectional"))
      (node (ref "U2") (pin "PC7") (pinfunction "PC7_PC7") (pintype "bidirectional"))
    )
    (net (code "61") (name "M1_ROW1") (class "Default")
      (node (ref "J2") (pin "6") (pinfunction "6_6") (pintype "bidirectional"))
      (node (ref "U2") (pin "PA1") (pinfunction "PA1_PA1") (pintype "bidirectional"))
    )
    (net (code "62") (name "M1_ROW2") (class "Default")
      (node (ref "J1") (pin "1") (pinfunction "1_1") (pintype "bidirectional"))
      (node (ref "U2") (pin "PC0") (pinfunction "PC0_PC0") (pintype "bidirectional"))
    )
    (net (code "63") (name "M1_ROW3") (class "Default")
      (node (ref "J2") (pin "4") (pinfunction "4_4") (pintype "bidirectional"))
      (node (ref "U2") (pin "PC1") (pinfunction "PC1_PC1") (pintype "bidirectional"))
    )
    (net (code "64") (name "M1_ROW4") (class "Default")
      (node (ref "J1") (pin "8") (pinfunction "8_8") (pintype "bidirectional"))
      (node (ref "U2") (pin "PC2") (pinfunction "PC2_PC2") (pintype "bidirectional"))
    )
    (net (code "65") (name "M1_ROW5") (class "Default")
      (node (ref "J1") (pin "2") (pinfunction "2_2") (pintype "bidirectional"))
      (node (ref "U2") (pin "PC3") (pinfunction "PC3_PC3") (pintype "bidirectional"))
    )
    (net (code "66") (name "M1_ROW6") (class "Default")
      (node (ref "J1") (pin "7") (pinfunction "7_7") (pintype "bidirectional"))
      (node (ref "U2") (pin "PC4") (pinfunction "PC4_PC4") (pintype "bidirectional"))
    )
    (net (code "67") (name "M1_ROW7") (class "Default")
      (node (ref "J1") (pin "4") (pinfunction "4_4") (pintype "bidirectional"))
      (node (ref "U2") (pin "PC5") (pinfunction "PC5_PC5") (pintype "bidirectional"))
    )
    (net (code "68") (name "M2_COL0") (class "Default")
      (node (ref "J4") (pin "8") (pinfunction "8_8") (pintype "bidirectional"))
      (node (ref "U5") (pin "O1") (pinfunction "O1_O1") (pintype "bidirectional"))
    )
    (net (code "69") (name "M2_COL0_SINK") (class "Default")
      (node (ref "U4") (pin "PD0") (pinfunction "PD0_PD0") (pintype "bidirectional"))
      (node (ref "U5") (pin "I1") (pinfunction "I1_I1") (pintype "bidirectional"))
    )
    (net (code "70") (name "M2_COL1") (class "Default")
      (node (ref "J4") (pin "7") (pinfunction "7_7") (pintype "bidirectional"))
      (node (ref "U5") (pin "O2") (pinfunction "O2_O2") (pintype "bidirectional"))
    )
    (net (code "71") (name "M2_COL1_SINK") (class "Default")
      (node (ref "U4") (pin "PD1") (pinfunction "PD1_PD1") (pintype "bidirectional"))
      (node (ref "U5") (pin "I2") (pinfunction "I2_I2") (pintype "bidirectional"))
    )
    (net (code "72") (name "M2_COL2") (class "Default")
      (node (ref "J4") (pin "3") (pinfunction "3_3") (pintype "bidirectional"))
      (node (ref "U5") (pin "O3") (pinfunction "O3_O3") (pintype "bidirectional"))
    )
    (net (code "73") (name "M2_COL2_SINK") (class "Default")
      (node (ref "U4") (pin "PD2") (pinfunction "PD2_PD2") (pintype "bidirectional"))
      (node (ref "U5") (pin "I3") (pinfunction "I3_I3") (pintype "bidirectional"))
    )
    (net (code "74") (name "M2_COL3") (class "Default")
      (node (ref "J3") (pin "3") (pinfunction "3_3") (pintype "bidirectional"))
      (node (ref "U5") (pin "O4") (pinfunction "O4_O4") (pintype "bidirectional"))
    )
    (net (code "75") (name "M2_COL3_SINK") (class "Default")
      (node (ref "U4") (pin "PD3") (pinfunction "PD3_PD3") (pintype "bidirectional"))
      (node (ref "U5") (pin "I4") (pinfunction "I4_I4") (pintype "bidirectional"))
    )
    (net (code "76") (name "M2_COL4") (class "Default")
      (node (ref "J4") (pin "2") (pinfunction "2_2") (pintype "bidirectional"))
      (node (ref "U5") (pin "O5") (pinfunction "O5_O5") (pintype "bidirectional"))
    )
    (net (code "77") (name "M2_COL4_SINK") (class "Default")
      (node (ref "U4") (pin "PD4") (pinfunction "PD4_PD4") (pintype "bidirectional"))
      (node (ref "U5") (pin "I5") (pinfunction "I5_I5") (pintype "bidirectional"))
    )
    (net (code "78") (name "M2_COL5") (class "Default")
      (node (ref "J3") (pin "5") (pinfunction "5_5") (pintype "bidirectional"))
      (node (ref "U5") (pin "O6") (pinfunction "O6_O6") (pintype "bidirectional"))
    )
    (net (code "79") (name "M2_COL5_SINK") (class "Default")
      (node (ref "U4") (pin "PD5") (pinfunction "PD5_PD5") (pintype "bidirectional"))
      (node (ref "U5") (pin "I6") (pinfunction "I6_I6") (pintype "bidirectional"))
    )
    (net (code "80") (name "M2_COL6") (class "Default")
      (node (ref "J3") (pin "6") (pinfunction "6_6") (pintype "bidirectional"))
      (node (ref "U5") (pin "O7") (pinfunction "O7_O7") (pintype "bidirectional"))
    )
    (net (code "81") (name "M2_COL6_SINK") (class "Default")
      (node (ref "U4") (pin "PD6") (pinfunction "PD6_PD6") (pintype "bidirectional"))
      (node (ref "U5") (pin "I7") (pinfunction "I7_I7") (pintype "bidirectional"))
    )
    (net (code "82") (name "M2_COL7") (class "Default")
      (node (ref "J4") (pin "5") (pinfunction "5_5") (pintype "bidirectional"))
      (node (ref "U5") (pin "O8") (pinfunction "O8_O8") (pintype "bidirectional"))
    )
    (net (code "83") (name "M2_COL7_SINK") (class "Default")
      (node (ref "U4") (pin "PD7") (pinfunction "PD7_PD7") (pintype "bidirectional"))
      (node (ref "U5") (pin "I8") (pinfunction "I8_I8") (pintype "bidirectional"))
    )
    (net (code "84") (name "M2_RESET") (class "Default")
      (node (ref "PROG2") (pin "5") (pinfunction "5_5") (pintype "passive"))
      (node (ref "R4") (pin "2") (pinfunction "2_2") (pintype "passive"))
      (node (ref "U4") (pin "PC6") (pinfunction "PC6_PC6") (pintype "bidirectional"))
    )
    (net (code "85") (name "M2_ROW0") (class "Default")
      (node (ref "J4") (pin "1") (pinfunction "1_1") (pintype "bidirectional"))
      (node (ref "U4") (pin "PC7") (pinfunction "PC7_PC7") (pintype "bidirectional"))
    )
    (net (code "86") (name "M2_ROW1") (class "Default")
      (node (ref "J4") (pin "6") (pinfunction "6_6") (pintype "bidirectional"))
      (node (ref "U4") (pin "PA1") (pinfunction "PA1_PA1") (pintype "bidirectional"))
    )
    (net (code "87") (name "M2_ROW2") (class "Default")
      (node (ref "J3") (pin "1") (pinfunction "1_1") (pintype "bidirectional"))
      (node (ref "U4") (pin "PC0") (pinfunction "PC0_PC0") (pintype "bidirectional"))
    )
    (net (code "88") (name "M2_ROW3") (class "Default")
      (node (ref "J4") (pin "4") (pinfunction "4_4") (pintype "bidirectional"))
      (node (ref "U4") (pin "PC1") (pinfunction "PC1_PC1") (pintype "bidirectional"))
    )
    (net (code "89") (name "M2_ROW4") (class "Default")
      (node (ref "J3") (pin "8") (pinfunction "8_8") (pintype "bidirectional"))
      (node (ref "U4") (pin "PC2") (pinfunction "PC2_PC2") (pintype "bidirectional"))
    )
    (net (code "90") (name "M2_ROW5") (class "Default")
      (node (ref "J3") (pin "2") (pinfunction "2_2") (pintype "bidirectional"))
      (node (ref "U4") (pin "PC3") (pinfunction "PC3_PC3") (pintype "bidirectional"))
    )
    (net (code "91") (name "M2_ROW6") (class "Default")
      (node (ref "J3") (pin "7") (pinfunction "7_7") (pintype "bidirectional"))
      (node (ref "U4") (pin "PC4") (pinfunction "PC4_PC4") (pintype "bidirectional"))
    )
    (net (code "92") (name "M2_ROW7") (class "Default")
      (node (ref "J3") (pin "4") (pinfunction "4_4") (pintype "bidirectional"))
      (node (ref "U4") (pin "PC5") (pinfunction "PC5_PC5") (pintype "bidirectional"))
    )
    (net (code "93") (name "M3_COL0") (class "Default")
      (node (ref "J6") (pin "8") (pinfunction "8_8") (pintype "bidirectional"))
      (node (ref "U7") (pin "O1") (pinfunction "O1_O1") (pintype "bidirectional"))
    )
    (net (code "94") (name "M3_COL0_SINK") (class "Default")
      (node (ref "U6") (pin "PD0") (pinfunction "PD0_PD0") (pintype "bidirectional"))
      (node (ref "U7") (pin "I1") (pinfunction "I1_I1") (pintype "bidirectional"))
    )
    (net (code "95") (name "M3_COL1") (class "Default")
      (node (ref "J6") (pin "7") (pinfunction "7_7") (pintype "bidirectional"))
      (node (ref "U7") (pin "O2") (pinfunction "O2_O2") (pintype "bidirectional"))
    )
    (net (code "96") (name "M3_COL1_SINK") (class "Default")
      (node (ref "U6") (pin "PD1") (pinfunction "PD1_PD1") (pintype "bidirectional"))
      (node (ref "U7") (pin "I2") (pinfunction "I2_I2") (pintype "bidirectional"))
    )
    (net (code "97") (name "M3_COL2") (class "Default")
      (node (ref "J6") (pin "3") (pinfunction "3_3") (pintype "bidirectional"))
      (node (ref "U7") (pin "O3") (pinfunction "O3_O3") (pintype "bidirectional"))
    )
    (net (code "98") (name "M3_COL2_SINK") (class "Default")
      (node (ref "U6") (pin "PD2") (pinfunction "PD2_PD2") (pintype "bidirectional"))
      (node (ref "U7") (pin "I3") (pinfunction "I3_I3") (pintype "bidirectional"))
    )
    (net (code "99") (name "M3_COL3") (class "Default")
      (node (ref "J5") (pin "3") (pinfunction "3_3") (pintype "bidirectional"))
      (node (ref "U7") (pin "O4") (pinfunction "O4_O4") (pintype "bidirectional"))
    )
    (net (code "100") (name "M3_COL3_SINK") (class "Default")
      (node (ref "U6") (pin "PD3") (pinfunction "PD3_PD3") (pintype "bidirectional"))
      (node (ref "U7") (pin "I4") (pinfunction "I4_I4") (pintype "bidirectional"))
    )
    (net (code "101") (name "M3_COL4") (class "Default")
      (node (ref "J6") (pin "2") (pinfunction "2_2") (pintype "bidirectional"))
      (node (ref "U7") (pin "O5") (pinfunction "O5_O5") (pintype "bidirectional"))
    )
    (net (code "102") (name "M3_COL4_SINK") (class "Default")
      (node (ref "U6") (pin "PD4") (pinfunction "PD4_PD4") (pintype "bidirectional"))
      (node (ref "U7") (pin "I5") (pinfunction "I5_I5") (pintype "bidirectional"))
    )
    (net (code "103") (name "M3_COL5") (class "Default")
      (node (ref "J5") (pin "5") (pinfunction "5_5") (pintype "bidirectional"))
      (node (ref "U7") (pin "O6") (pinfunction "O6_O6") (pintype "bidirectional"))
    )
    (net (code "104") (name "M3_COL5_SINK") (class "Default")
      (node (ref "U6") (pin "PD5") (pinfunction "PD5_PD5") (pintype "bidirectional"))
      (node (ref "U7") (pin "I6") (pinfunction "I6_I6") (pintype "bidirectional"))
    )
    (net (code "105") (name "M3_COL6") (class "Default")
      (node (ref "J5") (pin "6") (pinfunction "6_6") (pintype "bidirectional"))
      (node (ref "U7") (pin "O7") (pinfunction "O7_O7") (pintype "bidirectional"))
    )
    (net (code "106") (name "M3_COL6_SINK") (class "Default")
      (node (ref "U6") (pin "PD6") (pinfunction "PD6_PD6") (pintype "bidirectional"))
      (node (ref "U7") (pin "I7") (pinfunction "I7_I7") (pintype "bidirectional"))
    )
    (net (code "107") (name "M3_COL7") (class "Default")
      (node (ref "J6") (pin "5") (pinfunction "5_5") (pintype "bidirectional"))
      (node (ref "U7") (pin "O8") (pinfunction "O8_O8") (pintype "bidirectional"))
    )
    (net (code "108") (name "M3_COL7_SINK") (class "Default")
      (node (ref "U6") (pin "PD7") (pinfunction "PD7_PD7") (pintype "bidirectional"))
      (node (ref "U7") (pin "I8") (pinfunction "I8_I8") (pintype "bidirectional"))
    )
    (net (code "109") (name "M3_RESET") (class "Default")
      (node (ref "PROG3") (pin "5") (pinfunction "5_5") (pintype "passive"))
      (node (ref "R5") (pin "2") (pinfunction "2_2") (pintype "passive"))
      (node (ref "U6") (pin "PC6") (pinfunction "PC6_PC6") (pintype "bidirectional"))
    )
    (net (code "110") (name "M3_ROW0") (class "Default")
      (node (ref "J6") (pin "1") (pinfunction "1_1") (pintype "bidirectional"))
      (node (ref "U6") (pin "PC7") (pinfunction "PC7_PC7") (pintype "bidirectional"))
    )
    (net (code "111") (name "M3_ROW1") (class "Default")
      (node (ref "J6") (pin "6") (pinfunction "6_6") (pintype "bidirectional"))
      (node (ref "U6") (pin "PA1") (pinfunction "PA1_PA1") (pintype "bidirectional"))
    )
    (net (code "112") (name "M3_ROW2") (class "Default")
      (node (ref "J5") (pin "1") (pinfunction "1_1") (pintype "bidirectional"))
      (node (ref "U6") (pin "PC0") (pinfunction "PC0_PC0") (pintype "bidirectional"))
    )
    (net (code "113") (name "M3_ROW3") (class "Default")
      (node (ref "J6") (pin "4") (pinfunction "4_4") (pintype "bidirectional"))
      (node (ref "U6") (pin "PC1") (pinfunction "PC1_PC1") (pintype "bidirectional"))
    )
    (net (code "114") (name "M3_ROW4") (class "Default")
      (node (ref "J5") (pin "8") (pinfunction "8_8") (pintype "bidirectional"))
      (node (ref "U6") (pin "PC2") (pinfunction "PC2_PC2") (pintype "bidirectional"))
    )
    (net (code "115") (name "M3_ROW5") (class "Default")
      (node (ref "J5") (pin "2") (pinfunction "2_2") (pintype "bidirectional"))
      (node (ref "U6") (pin "PC3") (pinfunction "PC3_PC3") (pintype "bidirectional"))
    )
    (net (code "116") (name "M3_ROW6") (class "Default")
      (node (ref "J5") (pin "7") (pinfunction "7_7") (pintype "bidirectional"))
      (node (ref "U6") (pin "PC4") (pinfunction "PC4_PC4") (pintype "bidirectional"))
    )
    (net (code "117") (name "M3_ROW7") (class "Default")
      (node (ref "J5") (pin "4") (pinfunction "4_4") (pintype "bidirectional"))
      (node (ref "U6") (pin "PC5") (pinfunction "PC5_PC5") (pintype "bidirectional"))
    )
    (net (code "118") (name "M4_COL0") (class "Default")
      (node (ref "J8") (pin "8") (pinfunction "8_8") (pintype "bidirectional"))
      (node (ref "U9") (pin "O1") (pinfunction "O1_O1") (pintype "bidirectional"))
    )
    (net (code "119") (name "M4_COL0_SINK") (class "Default")
      (node (ref "U8") (pin "PD0") (pinfunction "PD0_PD0") (pintype "bidirectional"))
      (node (ref "U9") (pin "I1") (pinfunction "I1_I1") (pintype "bidirectional"))
    )
    (net (code "120") (name "M4_COL1") (class "Default")
      (node (ref "J8") (pin "7") (pinfunction "7_7") (pintype "bidirectional"))
      (node (ref "U9") (pin "O2") (pinfunction "O2_O2") (pintype "bidirectional"))
    )
    (net (code "121") (name "M4_COL1_SINK") (class "Default")
      (node (ref "U8") (pin "PD1") (pinfunction "PD1_PD1") (pintype "bidirectional"))
      (node (ref "U9") (pin "I2") (pinfunction "I2_I2") (pintype "bidirectional"))
    )
    (net (code "122") (name "M4_COL2") (class "Default")
      (node (ref "J8") (pin "3") (pinfunction "3_3") (pintype "bidirectional"))
      (node (ref "U9") (pin "O3") (pinfunction "O3_O3") (pintype "bidirectional"))
    )
    (net (code "123") (name "M4_COL2_SINK") (class "Default")
      (node (ref "U8") (pin "PD2") (pinfunction "PD2_PD2") (pintype "bidirectional"))
      (node (ref "U9") (pin "I3") (pinfunction "I3_I3") (pintype "bidirectional"))
    )
    (net (code "124") (name "M4_COL3") (class "Default")
      (node (ref "J7") (pin "3") (pinfunction "3_3") (pintype "bidirectional"))
      (node (ref "U9") (pin "O4") (pinfunction "O4_O4") (pintype "bidirectional"))
    )
    (net (code "125") (name "M4_COL3_SINK") (class "Default")
      (node (ref "U8") (pin "PD3") (pinfunction "PD3_PD3") (pintype "bidirectional"))
      (node (ref "U9") (pin "I4") (pinfunction "I4_I4") (pintype "bidirectional"))
    )
    (net (code "126") (name "M4_COL4") (class "Default")
      (node (ref "J8") (pin "2") (pinfunction "2_2") (pintype "bidirectional"))
      (node (ref "U9") (pin "O5") (pinfunction "O5_O5") (pintype "bidirectional"))
    )
    (net (code "127") (name "M4_COL4_SINK") (class "Default")
      (node (ref "U8") (pin "PD4") (pinfunction "PD4_PD4") (pintype "bidirectional"))
      (node (ref "U9") (pin "I5") (pinfunction "I5_I5") (pintype "bidirectional"))
    )
    (net (code "128") (name "M4_COL5") (class "Default")
      (node (ref "J7") (pin "5") (pinfunction "5_5") (pintype "bidirectional"))
      (node (ref "U9") (pin "O6") (pinfunction "O6_O6") (pintype "bidirectional"))
    )
    (net (code "129") (name "M4_COL5_SINK") (class "Default")
      (node (ref "U8") (pin "PD5") (pinfunction "PD5_PD5") (pintype "bidirectional"))
      (node (ref "U9") (pin "I6") (pinfunction "I6_I6") (pintype "bidirectional"))
    )
    (net (code "130") (name "M4_COL6") (class "Default")
      (node (ref "J7") (pin "6") (pinfunction "6_6") (pintype "bidirectional"))
      (node (ref "U9") (pin "O7") (pinfunction "O7_O7") (pintype "bidirectional"))
    )
    (net (code "131") (name "M4_COL6_SINK") (class "Default")
      (node (ref "U8") (pin "PD6") (pinfunction "PD6_PD6") (pintype "bidirectional"))
      (node (ref "U9") (pin "I7") (pinfunction "I7_I7") (pintype "bidirectional"))
    )
    (net (code "132") (name "M4_COL7") (class "Default")
      (node (ref "J8") (pin "5") (pinfunction "5_5") (pintype "bidirectional"))
      (node (ref "U9") (pin "O8") (pinfunction "O8_O8") (pintype "bidirectional"))
    )
    (net (code "133") (name "M4_COL7_SINK") (class "Default")
      (node (ref "U8") (pin "PD7") (pinfunction "PD7_PD7") (pintype "bidirectional"))
      (node (ref "U9") (pin "I8") (pinfunction "I8_I8") (pintype "bidirectional"))
    )
    (net (code "134") (name "M4_RESET") (class "Default")
      (node (ref "PROG4") (pin "5") (pinfunction "5_5") (pintype "passive"))
      (node (ref "R6") (pin "2") (pinfunction "2_2") (pintype "passive"))
      (node (ref "U8") (pin "PC6") (pinfunction "PC6_PC6") (pintype "bidirectional"))
    )
    (net (code "135") (name "M4_ROW0") (class "Default")
      (node (ref "J8") (pin "1") (pinfunction "1_1") (pintype "bidirectional"))
      (node (ref "U8") (pin "PC7") (pinfunction "PC7_PC7") (pintype "bidirectional"))
    )
    (net (code "136") (name "M4_ROW1") (class "Default")
      (node (ref "J8") (pin "6") (pinfunction "6_6") (pintype "bidirectional"))
      (node (ref "U8") (pin "PA1") (pinfunction "PA1_PA1") (pintype "bidirectional"))
    )
    (net (code "137") (name "M4_ROW2") (class "Default")
      (node (ref "J7") (pin "1") (pinfunction "1_1") (pintype "bidirectional"))
      (node (ref "U8") (pin "PC0") (pinfunction "PC0_PC0") (pintype "bidirectional"))
    )
    (net (code "138") (name "M4_ROW3") (class "Default")
      (node (ref "J8") (pin "4") (pinfunction "4_4") (pintype "bidirectional"))
      (node (ref "U8") (pin "PC1") (pinfunction "PC1_PC1") (pintype "bidirectional"))
    )
    (net (code "139") (name "M4_ROW4") (class "Default")
      (node (ref "J7") (pin "8") (pinfunction "8_8") (pintype "bidirectional"))
      (node (ref "U8") (pin "PC2") (pinfunction "PC2_PC2") (pintype "bidirectional"))
    )
    (net (code "140") (name "M4_ROW5") (class "Default")
      (node (ref "J7") (pin "2") (pinfunction "2_2") (pintype "bidirectional"))
      (node (ref "U8") (pin "PC3") (pinfunction "PC3_PC3") (pintype "bidirectional"))
    )
    (net (code "141") (name "M4_ROW6") (class "Default")
      (node (ref "J7") (pin "7") (pinfunction "7_7") (pintype "bidirectional"))
      (node (ref "U8") (pin "PC4") (pinfunction "PC4_PC4") (pintype "bidirectional"))
    )
    (net (code "142") (name "M4_ROW7") (class "Default")
      (node (ref "J7") (pin "4") (pinfunction "4_4") (pintype "bidirectional"))
      (node (ref "U8") (pin "PC5") (pinfunction "PC5_PC5") (pintype "bidirectional"))
    )
    (net (code "143") (name "Net-(U1-BYP)") (class "Default")
      (node (ref "C3") (pin "1") (pinfunction "1_1") (pintype "passive"))
      (node (ref "U1") (pin "4") (pinfunction "BYP_4") (pintype "bidirectional"))
    )
    (net (code "144") (name "Net-(U10-WP)") (class "Default")
      (node (ref "U10") (pin "7") (pinfunction "WP_7") (pintype "input"))
      (node (ref "WP") (pin "1") (pinfunction "P$1_1") (pintype "bidirectional"))
    )
    (net (code "145") (name "S2IN") (class "Default")
      (node (ref "PROG1") (pin "1") (pinfunction "1_1") (pintype "passive"))
      (node (ref "PROG2") (pin "4") (pinfunction "4_4") (pintype "passive"))
      (node (ref "U2") (pin "PB4") (pinfunction "PB4_PB4") (pintype "bidirectional"))
      (node (ref "U4") (pin "PB3") (pinfunction "PB3_PB3") (pintype "bidirectional"))
    )
    (net (code "146") (name "S3IN") (class "Default")
      (node (ref "PROG2") (pin "1") (pinfunction "1_1") (pintype "passive"))
      (node (ref "PROG3") (pin "4") (pinfunction "4_4") (pintype "passive"))
      (node (ref "U4") (pin "PB4") (pinfunction "PB4_PB4") (pintype "bidirectional"))
      (node (ref "U6") (pin "PB3") (pinfunction "PB3_PB3") (pintype "bidirectional"))
    )
    (net (code "147") (name "S4IN") (class "Default")
      (node (ref "PROG3") (pin "1") (pinfunction "1_1") (pintype "passive"))
      (node (ref "PROG4") (pin "4") (pinfunction "4_4") (pintype "passive"))
      (node (ref "U6") (pin "PB4") (pinfunction "PB4_PB4") (pintype "bidirectional"))
      (node (ref "U8") (pin "PB3") (pinfunction "PB3_PB3") (pintype "bidirectional"))
    )
    (net (code "148") (name "VCC") (class "Default")
      (node (ref "C1") (pin "1") (pinfunction "1_1") (pintype "passive"))
      (node (ref "C2") (pin "1") (pinfunction "1_1") (pintype "passive"))
      (node (ref "C4") (pin "1") (pinfunction "1_1") (pintype "passive"))
      (node (ref "C5") (pin "1") (pinfunction "1_1") (pintype "passive"))
      (node (ref "C6") (pin "1") (pinfunction "1_1") (pintype "passive"))
      (node (ref "C7") (pin "1") (pinfunction "1_1") (pintype "passive"))
      (node (ref "C8") (pin "1") (pinfunction "1_1") (pintype "passive"))
      (node (ref "J9") (pin "2") (pinfunction "2_2") (pintype "passive"))
      (node (ref "PROG1") (pin "2") (pinfunction "2_2") (pintype "passive"))
      (node (ref "PROG2") (pin "2") (pinfunction "2_2") (pintype "passive"))
      (node (ref "PROG3") (pin "2") (pinfunction "2_2") (pintype "passive"))
      (node (ref "PROG4") (pin "2") (pinfunction "2_2") (pintype "passive"))
      (node (ref "R1") (pin "2") (pinfunction "2_2") (pintype "passive"))
      (node (ref "R2") (pin "2") (pinfunction "2_2") (pintype "passive"))
      (node (ref "R3") (pin "1") (pinfunction "1_1") (pintype "passive"))
      (node (ref "R4") (pin "1") (pinfunction "1_1") (pintype "passive"))
      (node (ref "R5") (pin "1") (pinfunction "1_1") (pintype "passive"))
      (node (ref "R6") (pin "1") (pinfunction "1_1") (pintype "passive"))
      (node (ref "U1") (pin "1") (pinfunction "VDD_1") (pintype "bidirectional"))
      (node (ref "U1") (pin "8") (pinfunction "VDDIO_8") (pintype "bidirectional"))
      (node (ref "U10") (pin "8") (pinfunction "VCC_8") (pintype "power_in"))
      (node (ref "U2") (pin "AVCC") (pinfunction "AVCC_AVCC") (pintype "bidirectional"))
      (node (ref "U2") (pin "VCC") (pinfunction "VCC_VCC") (pintype "bidirectional"))
      (node (ref "U3") (pin "COMMON") (pinfunction "COMMON_COMMON") (pintype "bidirectional"))
      (node (ref "U4") (pin "AVCC") (pinfunction "AVCC_AVCC") (pintype "bidirectional"))
      (node (ref "U4") (pin "VCC") (pinfunction "VCC_VCC") (pintype "bidirectional"))
      (node (ref "U5") (pin "COMMON") (pinfunction "COMMON_COMMON") (pintype "bidirectional"))
      (node (ref "U6") (pin "AVCC") (pinfunction "AVCC_AVCC") (pintype "bidirectional"))
      (node (ref "U6") (pin "VCC") (pinfunction "VCC_VCC") (pintype "bidirectional"))
      (node (ref "U7") (pin "COMMON") (pinfunction "COMMON_COMMON") (pintype "bidirectional"))
      (node (ref "U8") (pin "AVCC") (pinfunction "AVCC_AVCC") (pintype "bidirectional"))
      (node (ref "U8") (pin "VCC") (pinfunction "VCC_VCC") (pintype "bidirectional"))
      (node (ref "U9") (pin "COMMON") (pinfunction "COMMON_COMMON") (pintype "bidirectional"))
    )
    (net (code "149") (name "unconnected-(B1-Pad1)") (class "Default")
      (node (ref "B1") (pin "1") (pinfunction "1_1") (pintype "bidirectional"))
    )
    (net (code "150") (name "unconnected-(B1-Pad4)") (class "Default")
      (node (ref "B1") (pin "4") (pinfunction "4_4") (pintype "bidirectional"))
    )
    (net (code "151") (name "unconnected-(B2-Pad1)") (class "Default")
      (node (ref "B2") (pin "1") (pinfunction "1_1") (pintype "bidirectional"))
    )
    (net (code "152") (name "unconnected-(B2-Pad4)") (class "Default")
      (node (ref "B2") (pin "4") (pinfunction "4_4") (pintype "bidirectional"))
    )
    (net (code "153") (name "unconnected-(B3-Pad1)") (class "Default")
      (node (ref "B3") (pin "1") (pinfunction "1_1") (pintype "bidirectional"))
    )
    (net (code "154") (name "unconnected-(B3-Pad3)") (class "Default")
      (node (ref "B3") (pin "3") (pinfunction "3_3") (pintype "bidirectional"))
    )
    (net (code "155") (name "unconnected-(B4-Pad1)") (class "Default")
      (node (ref "B4") (pin "1") (pinfunction "1_1") (pintype "bidirectional"))
    )
    (net (code "156") (name "unconnected-(B4-Pad3)") (class "Default")
      (node (ref "B4") (pin "3") (pinfunction "3_3") (pintype "bidirectional"))
    )
    (net (code "157") (name "unconnected-(B5-Pad1)") (class "Default")
      (node (ref "B5") (pin "1") (pinfunction "1_1") (pintype "bidirectional"))
    )
    (net (code "158") (name "unconnected-(B5-Pad3)") (class "Default")
      (node (ref "B5") (pin "3") (pinfunction "3_3") (pintype "bidirectional"))
    )
    (net (code "159") (name "unconnected-(B6-Pad1)") (class "Default")
      (node (ref "B6") (pin "1") (pinfunction "1_1") (pintype "bidirectional"))
    )
    (net (code "160") (name "unconnected-(B6-Pad3)") (class "Default")
      (node (ref "B6") (pin "3") (pinfunction "3_3") (pintype "bidirectional"))
    )
    (net (code "161") (name "unconnected-(B7-Pad2)") (class "Default")
      (node (ref "B7") (pin "2") (pinfunction "2_2") (pintype "bidirectional"))
    )
    (net (code "162") (name "unconnected-(B7-Pad4)") (class "Default")
      (node (ref "B7") (pin "4") (pinfunction "4_4") (pintype "bidirectional"))
    )
    (net (code "163") (name "unconnected-(B8-Pad2)") (class "Default")
      (node (ref "B8") (pin "2") (pinfunction "2_2") (pintype "bidirectional"))
    )
    (net (code "164") (name "unconnected-(B8-Pad4)") (class "Default")
      (node (ref "B8") (pin "4") (pinfunction "4_4") (pintype "bidirectional"))
    )
    (net (code "165") (name "unconnected-(U2-PadPA0)") (class "Default")
      (node (ref "U2") (pin "PA0") (pinfunction "PA0_PA0") (pintype "bidirectional"))
    )
    (net (code "166") (name "unconnected-(U2-PadPA2)") (class "Default")
      (node (ref "U2") (pin "PA2") (pinfunction "PA2_PA2") (pintype "bidirectional"))
    )
    (net (code "167") (name "unconnected-(U2-PadPA3)") (class "Default")
      (node (ref "U2") (pin "PA3") (pinfunction "PA3_PA3") (pintype "bidirectional"))
    )
    (net (code "168") (name "unconnected-(U2-PadPB0)") (class "Default")
      (node (ref "U2") (pin "PB0") (pinfunction "PB0_PB0") (pintype "bidirectional"))
    )
    (net (code "169") (name "unconnected-(U2-PadPB1)") (class "Default")
      (node (ref "U2") (pin "PB1") (pinfunction "PB1_PB1") (pintype "bidirectional"))
    )
    (net (code "170") (name "unconnected-(U2-PadPB6)") (class "Default")
      (node (ref "U2") (pin "PB6") (pinfunction "PB6_PB6") (pintype "bidirectional"))
    )
    (net (code "171") (name "unconnected-(U2-PadPB7)") (class "Default")
      (node (ref "U2") (pin "PB7") (pinfunction "PB7_PB7") (pintype "bidirectional"))
    )
    (net (code "172") (name "unconnected-(U4-PadPA0)") (class "Default")
      (node (ref "U4") (pin "PA0") (pinfunction "PA0_PA0") (pintype "bidirectional"))
    )
    (net (code "173") (name "unconnected-(U4-PadPA2)") (class "Default")
      (node (ref "U4") (pin "PA2") (pinfunction "PA2_PA2") (pintype "bidirectional"))
    )
    (net (code "174") (name "unconnected-(U4-PadPA3)") (class "Default")
      (node (ref "U4") (pin "PA3") (pinfunction "PA3_PA3") (pintype "bidirectional"))
    )
    (net (code "175") (name "unconnected-(U4-PadPB0)") (class "Default")
      (node (ref "U4") (pin "PB0") (pinfunction "PB0_PB0") (pintype "bidirectional"))
    )
    (net (code "176") (name "unconnected-(U4-PadPB1)") (class "Default")
      (node (ref "U4") (pin "PB1") (pinfunction "PB1_PB1") (pintype "bidirectional"))
    )
    (net (code "177") (name "unconnected-(U4-PadPB6)") (class "Default")
      (node (ref "U4") (pin "PB6") (pinfunction "PB6_PB6") (pintype "bidirectional"))
    )
    (net (code "178") (name "unconnected-(U4-PadPB7)") (class "Default")
      (node (ref "U4") (pin "PB7") (pinfunction "PB7_PB7") (pintype "bidirectional"))
    )
    (net (code "179") (name "unconnected-(U6-PadPA0)") (class "Default")
      (node (ref "U6") (pin "PA0") (pinfunction "PA0_PA0") (pintype "bidirectional"))
    )
    (net (code "180") (name "unconnected-(U6-PadPA2)") (class "Default")
      (node (ref "U6") (pin "PA2") (pinfunction "PA2_PA2") (pintype "bidirectional"))
    )
    (net (code "181") (name "unconnected-(U6-PadPA3)") (class "Default")
      (node (ref "U6") (pin "PA3") (pinfunction "PA3_PA3") (pintype "bidirectional"))
    )
    (net (code "182") (name "unconnected-(U6-PadPB0)") (class "Default")
      (node (ref "U6") (pin "PB0") (pinfunction "PB0_PB0") (pintype "bidirectional"))
    )
    (net (code "183") (name "unconnected-(U6-PadPB1)") (class "Default")
      (node (ref "U6") (pin "PB1") (pinfunction "PB1_PB1") (pintype "bidirectional"))
    )
    (net (code "184") (name "unconnected-(U6-PadPB6)") (class "Default")
      (node (ref "U6") (pin "PB6") (pinfunction "PB6_PB6") (pintype "bidirectional"))
    )
    (net (code "185") (name "unconnected-(U6-PadPB7)") (class "Default")
      (node (ref "U6") (pin "PB7") (pinfunction "PB7_PB7") (pintype "bidirectional"))
    )
    (net (code "186") (name "unconnected-(U8-PadPA0)") (class "Default")
      (node (ref "U8") (pin "PA0") (pinfunction "PA0_PA0") (pintype "bidirectional"))
    )
    (net (code "187") (name "unconnected-(U8-PadPA2)") (class "Default")
      (node (ref "U8") (pin "PA2") (pinfunction "PA2_PA2") (pintype "bidirectional"))
    )
    (net (code "188") (name "unconnected-(U8-PadPA3)") (class "Default")
      (node (ref "U8") (pin "PA3") (pinfunction "PA3_PA3") (pintype "bidirectional"))
    )
    (net (code "189") (name "unconnected-(U8-PadPB0)") (class "Default")
      (node (ref "U8") (pin "PB0") (pinfunction "PB0_PB0") (pintype "bidirectional"))
    )
    (net (code "190") (name "unconnected-(U8-PadPB1)") (class "Default")
      (node (ref "U8") (pin "PB1") (pinfunction "PB1_PB1") (pintype "bidirectional"))
    )
    (net (code "191") (name "unconnected-(U8-PadPB6)") (class "Default")
      (node (ref "U8") (pin "PB6") (pinfunction "PB6_PB6") (pintype "bidirectional"))
    )
    (net (code "192") (name "unconnected-(U8-PadPB7)") (class "Default")
      (node (ref "U8") (pin "PB7") (pinfunction "PB7_PB7") (pintype "bidirectional"))
    )
  )
)
